# pwr_regulator.net
KiCad netlist of a schematic drawn in Altium Designer
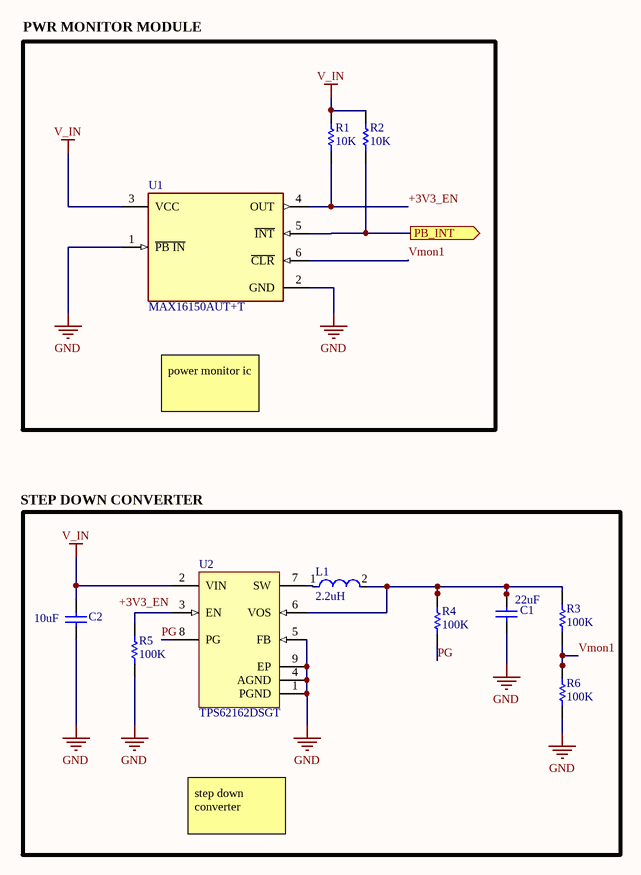
[diagram p0: pwr_regulator.SchDoc]

(export (version "E")
  (design (tool "Eeschema 10.0.6"))
  (components
    (comp (ref "C1")
      (value "22uF")
      (footprint "KEMT-1206-2_M")
      (description "CAP, Ceramic, 0.1 uF, +/- 10%, 50 V, -55 to 125 degC, 1206 (3216 Metric), RoHS, Tape and Reel")
      (fields (field (name "MANUFACTURER") "Kemet"))
      (libsource (lib "Altium Content Vault") (part "CAP-NP-2"))
    )
    (comp (ref "C2")
      (value "10uF")
      (footprint "KEMT-1206-2_M")
      (description "CAP, Ceramic, 0.1 uF, +/- 10%, 50 V, -55 to 125 degC, 1206 (3216 Metric), RoHS, Tape and Reel")
      (fields (field (name "MANUFACTURER") "Kemet"))
      (libsource (lib "Altium Content Vault") (part "CAP-NP-2"))
    )
    (comp (ref "L1")
      (value "2.2uH")
      (footprint "FP-LQH31CN_03-MFG")
      (description "Wire Wound Ferrite Inductor for General Circuits 56μH ±10% 11.57Ω 50mA 1206")
      (fields (field (name "TOLERANCE") "10%"))
      (libsource (lib "Altium Content Vault") (part "725321dda6339637d4d059423bc1c3c"))
    )
    (comp (ref "R1")
      (value "10K")
      (footprint "RESC3216X70X50NL05T20")
      (fields (field (name "MANUFACTURER") "Panasonic") (field (name "PART NUMBER") "ERJ-8GEY0R00V"))
      (libsource (lib "Altium Content Vault") (part "RES"))
    )
    (comp (ref "R2")
      (value "10K")
      (footprint "RESC3216X70X50NL05T20")
      (fields (field (name "MANUFACTURER") "Panasonic") (field (name "PART NUMBER") "ERJ-8GEY0R00V"))
      (libsource (lib "Altium Content Vault") (part "RES"))
    )
    (comp (ref "R3")
      (value "100K")
      (footprint "RESC3216X70X50NL05T20")
      (fields (field (name "MANUFACTURER") "Panasonic") (field (name "PART NUMBER") "ERJ-8GEY0R00V"))
      (libsource (lib "Altium Content Vault") (part "RES"))
    )
    (comp (ref "R4")
      (value "100K")
      (footprint "RESC3216X70X50NL05T20")
      (fields (field (name "MANUFACTURER") "Panasonic") (field (name "PART NUMBER") "ERJ-8GEY0R00V"))
      (libsource (lib "Altium Content Vault") (part "RES"))
    )
    (comp (ref "R5")
      (value "100K")
      (footprint "RESC3216X70X50NL05T20")
      (fields (field (name "MANUFACTURER") "Panasonic") (field (name "PART NUMBER") "ERJ-8GEY0R00V"))
      (libsource (lib "Altium Content Vault") (part "RES"))
    )
    (comp (ref "R6")
      (value "100K")
      (footprint "RESC3216X70X50NL05T20")
      (fields (field (name "MANUFACTURER") "Panasonic") (field (name "PART NUMBER") "ERJ-8GEY0R00V"))
      (libsource (lib "Altium Content Vault") (part "RES"))
    )
    (comp (ref "U1")
      (value "MAX16150AUT+T")
      (footprint "FP-U6-1-MFG")
      (description "IC SUPERVISOR 1 CHANNEL SOT23-6")
      (libsource (lib "Altium Content Vault") (part "36a392858d03d148bb8ce7f45f4b5f9"))
    )
    (comp (ref "U2")
      (value "TPS62162DSGT")
      (footprint "DSG0008A_V")
      (fields (field (name "MANUFACTURER") "Texas Instruments"))
      (libsource (lib "Altium Content Vault") (part "TI-TPS62162DSG8-1600X900TP"))
    )
  )
  (nets
    (net (code "1") (name "/+3V3_EN") (class "Default")
      (node (ref "R1") (pin "1") (pinfunction "1_1") (pintype "passive"))
      (node (ref "U1") (pin "4") (pinfunction "OUT_4") (pintype "output"))
    )
    (net (code "2") (name "/PB_INT") (class "Default")
      (node (ref "R2") (pin "1") (pinfunction "1_1") (pintype "passive"))
      (node (ref "U1") (pin "5") (pinfunction "~{INT}_5") (pintype "input"))
    )
    (net (code "3") (name "/PG") (class "Default")
      (node (ref "R4") (pin "1") (pinfunction "1_1") (pintype "passive"))
      (node (ref "U2") (pin "8") (pinfunction "PG_8") (pintype "tri_state"))
    )
    (net (code "4") (name "/Vmon1") (class "Default")
      (node (ref "R3") (pin "1") (pinfunction "1_1") (pintype "passive"))
      (node (ref "R6") (pin "2") (pinfunction "2_2") (pintype "passive"))
      (node (ref "U1") (pin "6") (pinfunction "~{CLR}_6") (pintype "input"))
    )
    (net (code "5") (name "GND") (class "Default")
      (node (ref "C1") (pin "1") (pinfunction "1_1") (pintype "passive"))
      (node (ref "C2") (pin "1") (pinfunction "1_1") (pintype "passive"))
      (node (ref "R5") (pin "1") (pinfunction "1_1") (pintype "passive"))
      (node (ref "R6") (pin "1") (pinfunction "1_1") (pintype "passive"))
      (node (ref "U1") (pin "1") (pinfunction "~{PB_IN}_1") (pintype "input"))
      (node (ref "U1") (pin "2") (pinfunction "GND_2") (pintype "power_in"))
      (node (ref "U2") (pin "1") (pinfunction "PGND_1") (pintype "power_in"))
      (node (ref "U2") (pin "4") (pinfunction "AGND_4") (pintype "power_in"))
      (node (ref "U2") (pin "5") (pinfunction "FB_5") (pintype "input"))
      (node (ref "U2") (pin "9") (pinfunction "EP_9") (pintype "power_in"))
    )
    (net (code "6") (name "Net-(U2-EN)") (class "Default")
      (node (ref "R5") (pin "2") (pinfunction "2_2") (pintype "passive"))
      (node (ref "U2") (pin "3") (pinfunction "EN_3") (pintype "input"))
    )
    (net (code "7") (name "Net-(U2-SW)") (class "Default")
      (node (ref "L1") (pin "1") (pinfunction "1_1") (pintype "passive"))
      (node (ref "U2") (pin "7") (pinfunction "SW_7") (pintype "power_in"))
    )
    (net (code "8") (name "Net-(U2-VOS)") (class "Default")
      (node (ref "C1") (pin "2") (pinfunction "2_2") (pintype "passive"))
      (node (ref "L1") (pin "2") (pinfunction "2_2") (pintype "passive"))
      (node (ref "R3") (pin "2") (pinfunction "2_2") (pintype "passive"))
      (node (ref "R4") (pin "2") (pinfunction "2_2") (pintype "passive"))
      (node (ref "U2") (pin "6") (pinfunction "VOS_6") (pintype "input"))
    )
    (net (code "9") (name "V_IN") (class "Default")
      (node (ref "C2") (pin "2") (pinfunction "2_2") (pintype "passive"))
      (node (ref "R1") (pin "2") (pinfunction "2_2") (pintype "passive"))
      (node (ref "U1") (pin "3") (pinfunction "VCC_3") (pintype "power_in"))
      (node (ref "U2") (pin "2") (pinfunction "VIN_2") (pintype "power_in"))
    )
    (net (code "10") (name "unconnected-(R2-Pad2)") (class "Default")
      (node (ref "R2") (pin "2") (pinfunction "2_2") (pintype "passive"))
    )
  )
)
